# 2014_FDP_Generic_Port_Strat.net
KiCad netlist of a schematic drawn in Altium Designer
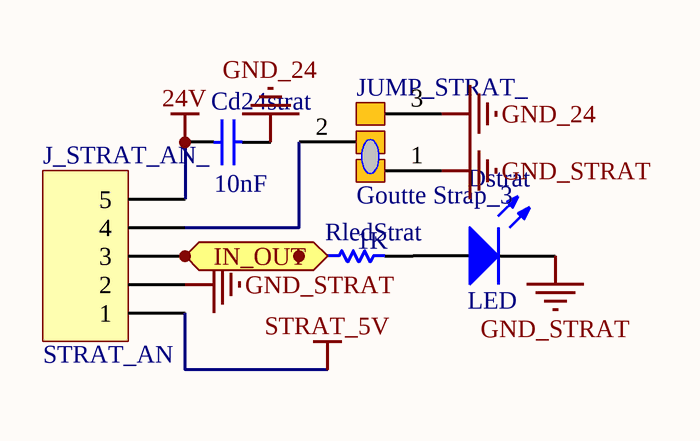
[diagram p0: 2014_FDP_Generic_Port_Strat.SchDoc]

(export (version "E")
  (design (tool "Eeschema 10.0.6"))
  (components
    (comp (ref "Cd24strat")
      (value "10nF")
      (footprint "C0805_N")
      (description "Capacitor")
      (fields (field (name "PUBLISHER") "Altium Limited"))
      (libsource (lib "_ROBOT") (part "Condensateur"))
    )
    (comp (ref "Dstrat")
      (value "LED")
      (footprint "LED_0805")
      (description "Typical LED")
      (fields (field (name "PUBLISHER") "Altium Limited"))
      (libsource (lib "_ROBOT") (part "LED"))
    )
    (comp (ref "JUMP_STRAT_")
      (value "Goutte Strap_3")
      (footprint "Goutte Strap_3")
      (fields (field (name "PUBLISHER") "Damien Guitton"))
      (libsource (lib "DG_Connecteur") (part "Goutte Strap_3"))
    )
    (comp (ref "J_STRAT_AN_")
      (value "STRAT_AN")
      (footprint "HE14_5")
      (description "Header, 5-Pin")
      (fields (field (name "PUBLISHER") "Altium Limited"))
      (libsource (lib "Connecteur") (part "BARRETTE5"))
    )
    (comp (ref "RledStrat")
      (value "1K")
      (footprint "R1206_N")
      (description "Resistor")
      (fields (field (name "PUBLISHER") "Altium Limited"))
      (libsource (lib "_ROBOT") (part "Resistor"))
    )
  )
  (nets
    (net (code "1") (name "/IN_OUT") (class "Default")
      (node (ref "J_STRAT_AN_") (pin "3") (pinfunction "3_3") (pintype "passive"))
      (node (ref "RledStrat") (pin "1") (pinfunction "1_1") (pintype "passive"))
    )
    (net (code "2") (name "24V") (class "Default")
      (node (ref "Cd24strat") (pin "1") (pinfunction "1_1") (pintype "passive"))
      (node (ref "J_STRAT_AN_") (pin "5") (pinfunction "5_5") (pintype "passive"))
    )
    (net (code "3") (name "GND_24") (class "Default")
      (node (ref "Cd24strat") (pin "2") (pinfunction "2_2") (pintype "passive"))
      (node (ref "JUMP_STRAT_") (pin "3") (pinfunction "3_3") (pintype "passive"))
    )
    (net (code "4") (name "GND_STRAT") (class "Default")
      (node (ref "Dstrat") (pin "2") (pinfunction "K_2") (pintype "passive"))
      (node (ref "JUMP_STRAT_") (pin "1") (pinfunction "1_1") (pintype "passive"))
      (node (ref "J_STRAT_AN_") (pin "2") (pinfunction "2_2") (pintype "passive"))
    )
    (net (code "5") (name "Net-(Dstrat-A)") (class "Default")
      (node (ref "Dstrat") (pin "1") (pinfunction "A_1") (pintype "passive"))
      (node (ref "RledStrat") (pin "2") (pinfunction "2_2") (pintype "passive"))
    )
    (net (code "6") (name "Net-(JUMP_STRAT_-Pad2)") (class "Default")
      (node (ref "JUMP_STRAT_") (pin "2") (pinfunction "2_2") (pintype "passive"))
      (node (ref "J_STRAT_AN_") (pin "4") (pinfunction "4_4") (pintype "passive"))
    )
    (net (code "7") (name "STRAT_5V") (class "Default")
      (node (ref "J_STRAT_AN_") (pin "1") (pinfunction "1_1") (pintype "passive"))
    )
  )
)
